# LiFePO4_Charger_V2.net
KiCad netlist of a schematic drawn in EAGLE
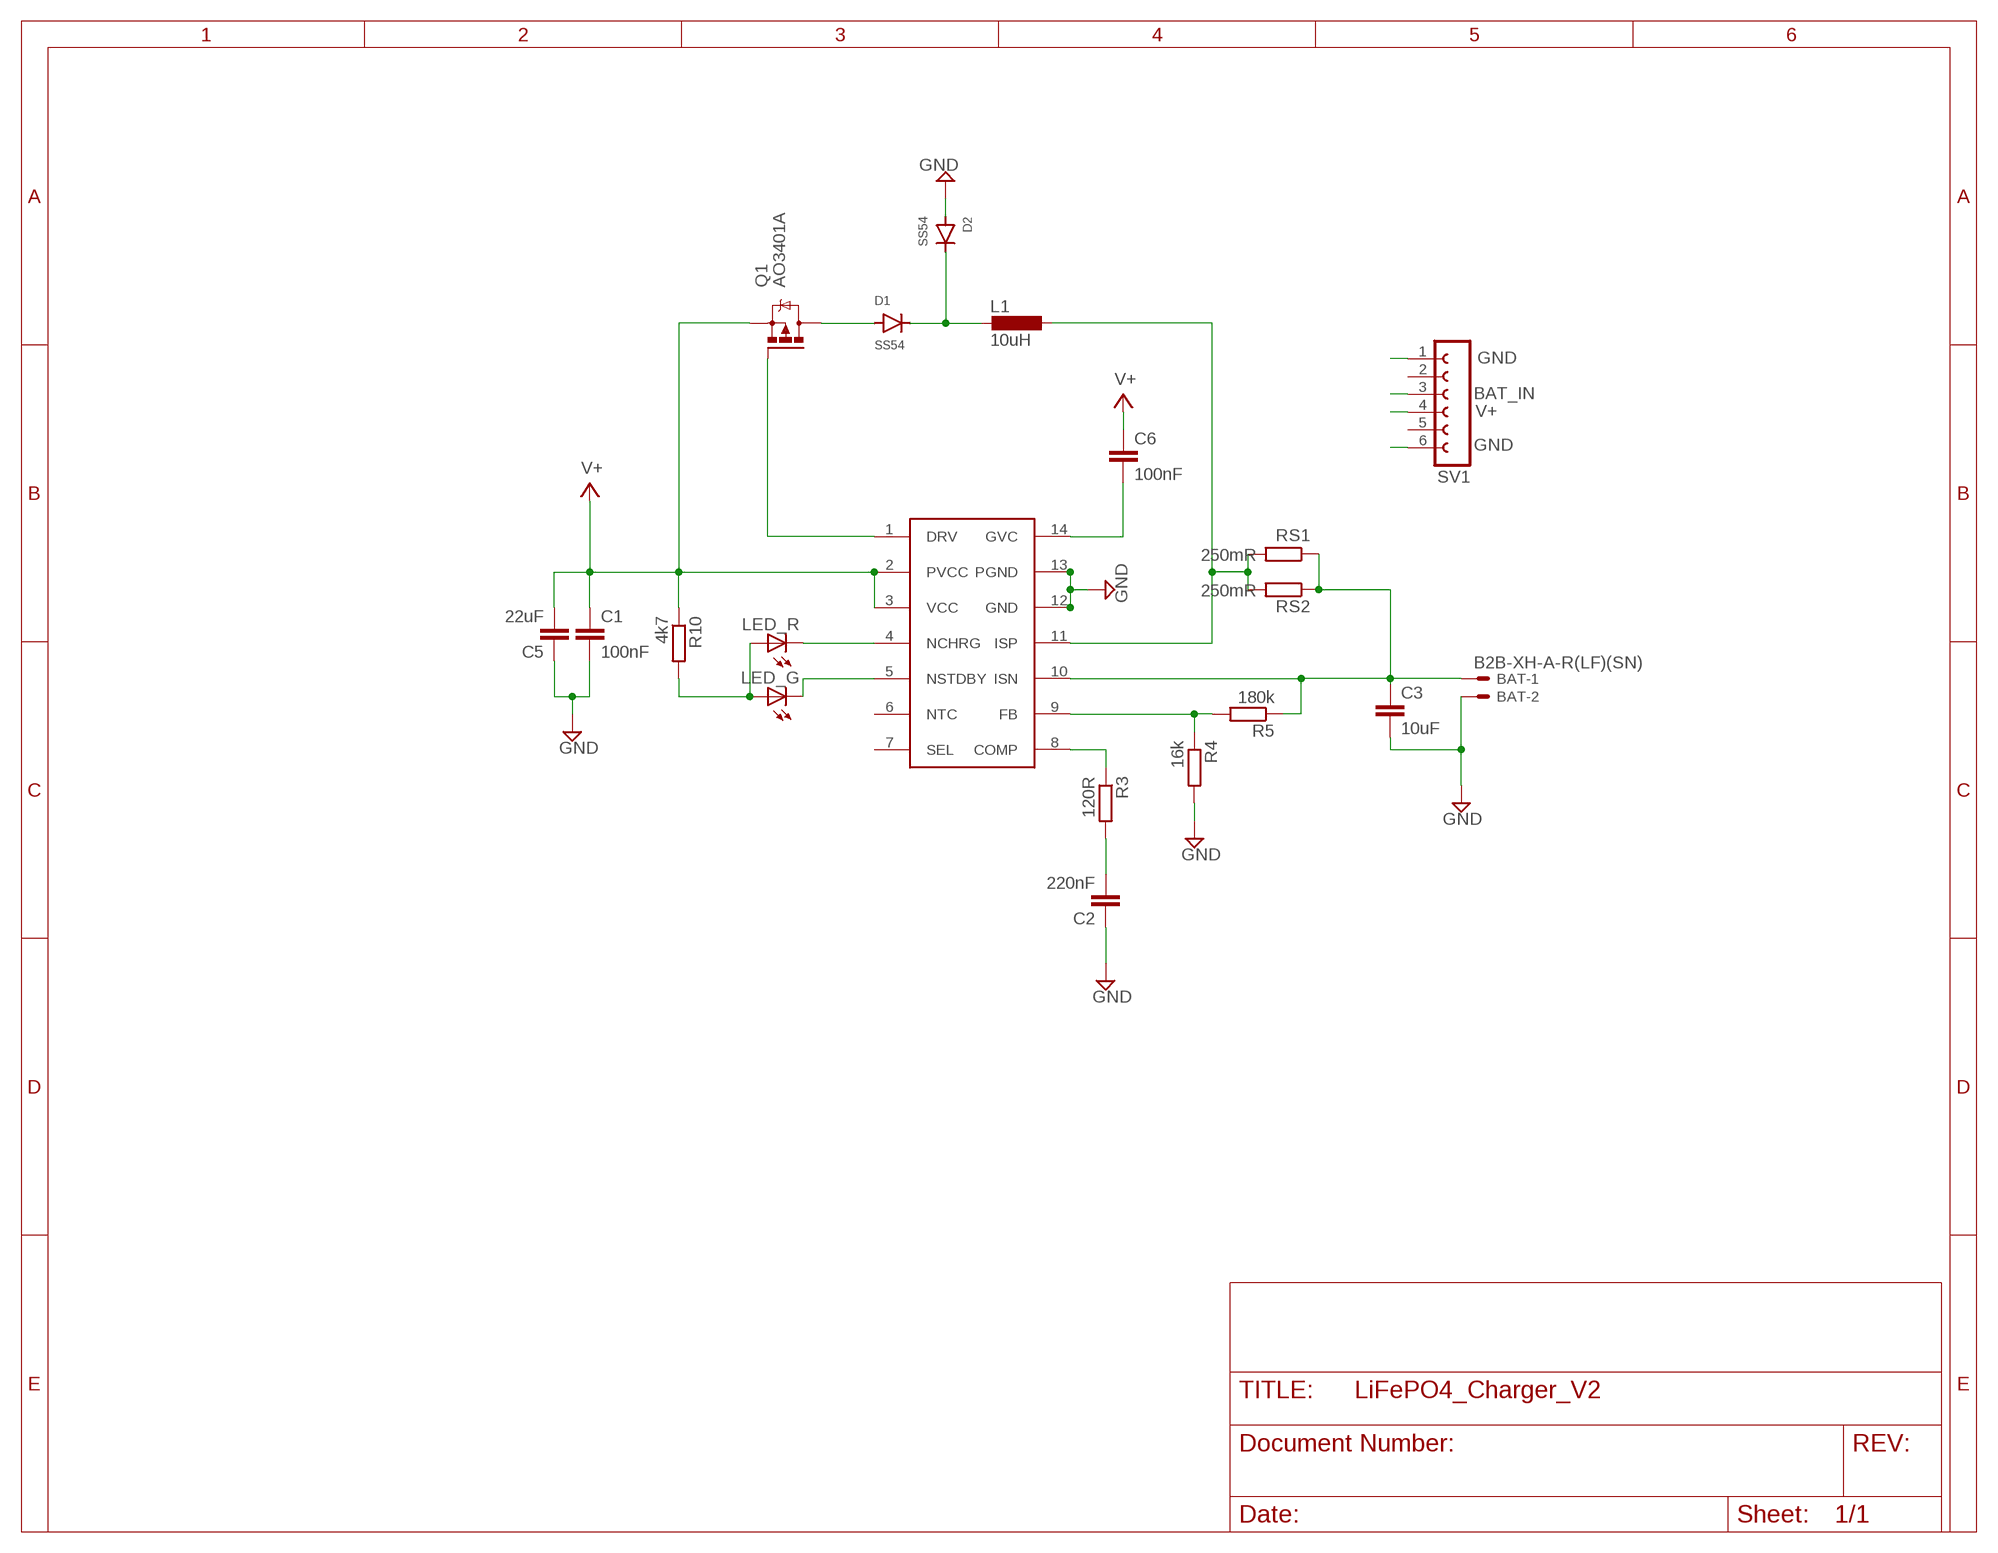
[diagram p0: schematic, sheet 1]

(export (version "E")
  (design (tool "Eeschema 10.0.6"))
  (components
    (comp (ref "BAT")
      (value "B2B-XH-A-R(LF)(SN)")
      (footprint "eagle-import:JST-XH-02-PACKAGE-LONG-PAD")
      (libsource (lib "eagle-import") (part "JST-XH-02-PIN-LONG-PAD"))
    )
    (comp (ref "C1")
      (value "100nF")
      (footprint "eagle-import:C0805")
      (libsource (lib "eagle-import") (part "C-EUC0805"))
    )
    (comp (ref "C2")
      (value "220nF")
      (footprint "eagle-import:C0805")
      (libsource (lib "eagle-import") (part "C-EUC0805"))
    )
    (comp (ref "C3")
      (value "10uF")
      (footprint "eagle-import:C0805")
      (libsource (lib "eagle-import") (part "C-EUC0805"))
    )
    (comp (ref "C5")
      (value "22uF")
      (footprint "eagle-import:C0805")
      (libsource (lib "eagle-import") (part "C-EUC0805"))
    )
    (comp (ref "C6")
      (value "100nF")
      (footprint "eagle-import:C0805")
      (libsource (lib "eagle-import") (part "C-EUC0805"))
    )
    (comp (ref "D1")
      (value "SS54")
      (footprint "eagle-import:SMA")
      (libsource (lib "eagle-import") (part "S1M"))
    )
    (comp (ref "D2")
      (value "SS54")
      (footprint "eagle-import:SMA")
      (libsource (lib "eagle-import") (part "S1M"))
    )
    (comp (ref "IC1")
      (value "SLM6900")
      (footprint "eagle-import:TSSOP14")
      (libsource (lib "eagle-import") (part "SLM9000TSSOP14L"))
    )
    (comp (ref "L1")
      (value "10uH")
      (footprint "eagle-import:FXL0630-100-M")
      (libsource (lib "eagle-import") (part "FXL0630-100-M"))
    )
    (comp (ref "LED_G")
      (value "LEDCHIPLED_0805")
      (footprint "eagle-import:CHIPLED_0805")
      (libsource (lib "eagle-import") (part "LEDCHIPLED_0805"))
    )
    (comp (ref "LED_R")
      (value "LEDCHIPLED_0805")
      (footprint "eagle-import:CHIPLED_0805")
      (libsource (lib "eagle-import") (part "LEDCHIPLED_0805"))
    )
    (comp (ref "Q1")
      (value "AO3401A")
      (footprint "eagle-import:MICRO3")
      (libsource (lib "eagle-import") (part "IRLML5203"))
    )
    (comp (ref "R3")
      (value "120R")
      (footprint "eagle-import:R0603")
      (libsource (lib "eagle-import") (part "R-EU_R0603"))
    )
    (comp (ref "R4")
      (value "16k")
      (footprint "eagle-import:R0805")
      (libsource (lib "eagle-import") (part "R-EU_R0805"))
    )
    (comp (ref "R5")
      (value "180k")
      (footprint "eagle-import:R0603")
      (libsource (lib "eagle-import") (part "R-EU_R0603"))
    )
    (comp (ref "R10")
      (value "4k7")
      (footprint "eagle-import:R0603")
      (libsource (lib "eagle-import") (part "R-EU_R0603"))
    )
    (comp (ref "RS1")
      (value "250mR")
      (footprint "eagle-import:R1206")
      (libsource (lib "eagle-import") (part "R-EU_R1206"))
    )
    (comp (ref "RS2")
      (value "250mR")
      (footprint "eagle-import:R1206")
      (libsource (lib "eagle-import") (part "R-EU_R1206"))
    )
    (comp (ref "SV1")
      (value "FE06W")
      (footprint "eagle-import:FE06W")
      (libsource (lib "eagle-import") (part "FE06W"))
    )
  )
  (nets
    (net (code "1") (name "/BAT_IN") (class "Default")
      (node (ref "BAT") (pin "1") (pinfunction "S_1") (pintype "passive"))
      (node (ref "C3") (pin "1") (pinfunction "1_1") (pintype "passive"))
      (node (ref "IC1") (pin "10") (pinfunction "ISN_10") (pintype "bidirectional"))
      (node (ref "R5") (pin "1") (pinfunction "1_1") (pintype "passive"))
      (node (ref "RS1") (pin "1") (pinfunction "1_1") (pintype "passive"))
      (node (ref "RS2") (pin "1") (pinfunction "1_1") (pintype "passive"))
      (node (ref "SV1") (pin "3") (pinfunction "3_3") (pintype "passive"))
    )
    (net (code "2") (name "GND") (class "Default")
      (node (ref "BAT") (pin "2") (pinfunction "S_2") (pintype "passive"))
      (node (ref "C1") (pin "2") (pinfunction "2_2") (pintype "passive"))
      (node (ref "C2") (pin "1") (pinfunction "1_1") (pintype "passive"))
      (node (ref "C3") (pin "2") (pinfunction "2_2") (pintype "passive"))
      (node (ref "C5") (pin "1") (pinfunction "1_1") (pintype "passive"))
      (node (ref "D2") (pin "A") (pinfunction "A_A") (pintype "passive"))
      (node (ref "IC1") (pin "12") (pinfunction "GND_12") (pintype "power_in"))
      (node (ref "IC1") (pin "13") (pinfunction "PGND_13") (pintype "power_in"))
      (node (ref "R4") (pin "2") (pinfunction "2_2") (pintype "passive"))
      (node (ref "SV1") (pin "1") (pinfunction "1_1") (pintype "passive"))
      (node (ref "SV1") (pin "6") (pinfunction "6_6") (pintype "passive"))
    )
    (net (code "3") (name "Net-(C2-Pad2)") (class "Default")
      (node (ref "C2") (pin "2") (pinfunction "2_2") (pintype "passive"))
      (node (ref "R3") (pin "2") (pinfunction "2_2") (pintype "passive"))
    )
    (net (code "4") (name "Net-(IC1-COMP)") (class "Default")
      (node (ref "IC1") (pin "8") (pinfunction "COMP_8") (pintype "bidirectional"))
      (node (ref "R3") (pin "1") (pinfunction "1_1") (pintype "passive"))
    )
    (net (code "5") (name "Net-(IC1-DRV)") (class "Default")
      (node (ref "IC1") (pin "1") (pinfunction "DRV_1") (pintype "output"))
      (node (ref "Q1") (pin "1") (pinfunction "G_1") (pintype "passive"))
    )
    (net (code "6") (name "Net-(IC1-FB)") (class "Default")
      (node (ref "IC1") (pin "9") (pinfunction "FB_9") (pintype "bidirectional"))
      (node (ref "R4") (pin "1") (pinfunction "1_1") (pintype "passive"))
      (node (ref "R5") (pin "2") (pinfunction "2_2") (pintype "passive"))
    )
    (net (code "7") (name "Net-(IC1-GVC)") (class "Default")
      (node (ref "C6") (pin "2") (pinfunction "2_2") (pintype "passive"))
      (node (ref "IC1") (pin "14") (pinfunction "GVC_14") (pintype "bidirectional"))
    )
    (net (code "8") (name "Net-(IC1-ISP)") (class "Default")
      (node (ref "IC1") (pin "11") (pinfunction "ISP_11") (pintype "bidirectional"))
      (node (ref "L1") (pin "P$2") (pinfunction "2_P$2") (pintype "passive"))
      (node (ref "RS1") (pin "2") (pinfunction "2_2") (pintype "passive"))
      (node (ref "RS2") (pin "2") (pinfunction "2_2") (pintype "passive"))
    )
    (net (code "9") (name "Net-(IC1-NCHRG)") (class "Default")
      (node (ref "IC1") (pin "4") (pinfunction "NCHRG_4") (pintype "bidirectional"))
      (node (ref "LED_R") (pin "C") (pinfunction "C_C") (pintype "passive"))
    )
    (net (code "10") (name "Net-(IC1-NSTDBY)") (class "Default")
      (node (ref "IC1") (pin "5") (pinfunction "NSTDBY_5") (pintype "bidirectional"))
      (node (ref "LED_G") (pin "C") (pinfunction "C_C") (pintype "passive"))
    )
    (net (code "11") (name "Net-(L1-1)") (class "Default")
      (node (ref "D1") (pin "C") (pinfunction "C_C") (pintype "passive"))
      (node (ref "D2") (pin "C") (pinfunction "C_C") (pintype "passive"))
      (node (ref "L1") (pin "P$1") (pinfunction "1_P$1") (pintype "passive"))
    )
    (net (code "12") (name "Net-(LED_G-PadA)") (class "Default")
      (node (ref "LED_G") (pin "A") (pinfunction "A_A") (pintype "passive"))
      (node (ref "LED_R") (pin "A") (pinfunction "A_A") (pintype "passive"))
      (node (ref "R10") (pin "2") (pinfunction "2_2") (pintype "passive"))
    )
    (net (code "13") (name "Net-(Q1-D)") (class "Default")
      (node (ref "D1") (pin "A") (pinfunction "A_A") (pintype "passive"))
      (node (ref "Q1") (pin "3") (pinfunction "D_3") (pintype "passive"))
    )
    (net (code "14") (name "V+") (class "Default")
      (node (ref "C1") (pin "1") (pinfunction "1_1") (pintype "passive"))
      (node (ref "C5") (pin "2") (pinfunction "2_2") (pintype "passive"))
      (node (ref "C6") (pin "1") (pinfunction "1_1") (pintype "passive"))
      (node (ref "IC1") (pin "2") (pinfunction "PVCC_2") (pintype "power_in"))
      (node (ref "IC1") (pin "3") (pinfunction "VCC_3") (pintype "power_in"))
      (node (ref "Q1") (pin "2") (pinfunction "S_2") (pintype "passive"))
      (node (ref "R10") (pin "1") (pinfunction "1_1") (pintype "passive"))
      (node (ref "SV1") (pin "4") (pinfunction "4_4") (pintype "passive"))
    )
    (net (code "15") (name "unconnected-(IC1-NTC-Pad6)") (class "Default")
      (node (ref "IC1") (pin "6") (pinfunction "NTC_6") (pintype "bidirectional"))
    )
    (net (code "16") (name "unconnected-(IC1-SEL-Pad7)") (class "Default")
      (node (ref "IC1") (pin "7") (pinfunction "SEL_7") (pintype "input"))
    )
    (net (code "17") (name "unconnected-(SV1-Pad2)") (class "Default")
      (node (ref "SV1") (pin "2") (pinfunction "2_2") (pintype "passive"))
    )
    (net (code "18") (name "unconnected-(SV1-Pad5)") (class "Default")
      (node (ref "SV1") (pin "5") (pinfunction "5_5") (pintype "passive"))
    )
  )
)
